# oneboard2.net
KiCad netlist of a schematic drawn in EAGLE
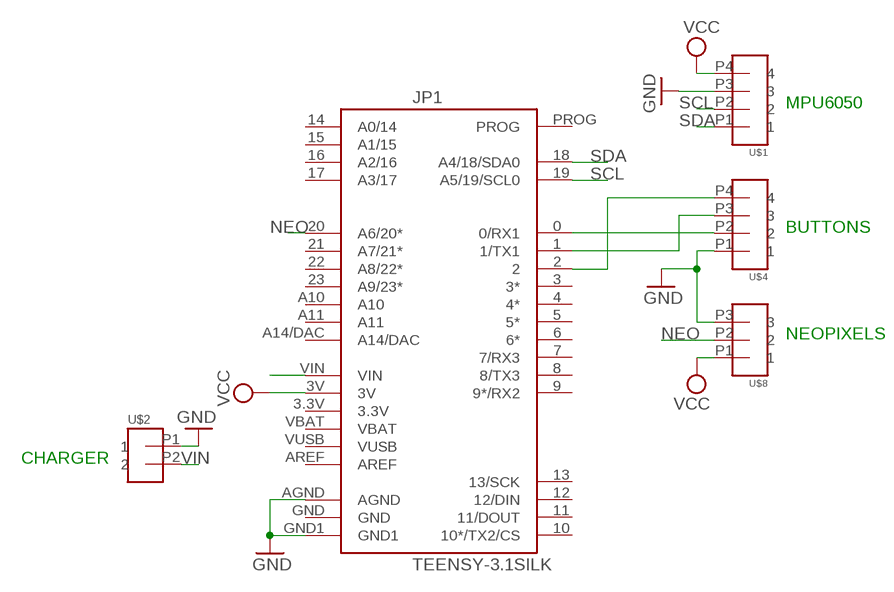
[diagram p0: schematic, sheet 1]

(export (version "E")
  (design (tool "Eeschema 10.0.6"))
  (components
    (comp (ref "JP1")
      (value "TEENSY-3.1SILK")
      (footprint "eagle-import:TEENSY-3.1")
      (libsource (lib "eagle-import") (part "TEENSY-3.1SILK"))
    )
    (comp (ref "U$1")
      (value "PTSM0,4-HH-2,5-SMD-R44")
      (footprint "eagle-import:M04_SMD_RIGHT")
      (libsource (lib "eagle-import") (part "PTSM0,4-HH-2,5-SMD-R44"))
    )
    (comp (ref "U$2")
      (value "PTSM0,2-HH-2,5-SMD-R32")
      (footprint "eagle-import:M02_SMD_RIGHT")
      (libsource (lib "eagle-import") (part "PTSM0,2-HH-2,5-SMD-R32"))
    )
    (comp (ref "U$4")
      (value "PTSM0,4-HH-2,5-SMD-R44")
      (footprint "eagle-import:M04_SMD_RIGHT")
      (libsource (lib "eagle-import") (part "PTSM0,4-HH-2,5-SMD-R44"))
    )
    (comp (ref "U$8")
      (value "PTSM0,3-HH-2,5-SMD-R44")
      (footprint "eagle-import:M03_SMD_RIGHT")
      (libsource (lib "eagle-import") (part "PTSM0,3-HH-2,5-SMD-R44"))
    )
  )
  (nets
    (net (code "1") (name "/NEO") (class "Default")
      (node (ref "JP1") (pin "20") (pinfunction "A6/20*_20") (pintype "bidirectional"))
      (node (ref "U$8") (pin "P2") (pinfunction "2_P2") (pintype "bidirectional"))
    )
    (net (code "2") (name "/SCL") (class "Default")
      (node (ref "JP1") (pin "19") (pinfunction "A5/19/SCL0_19") (pintype "bidirectional"))
      (node (ref "U$1") (pin "P2") (pinfunction "2_P2") (pintype "bidirectional"))
    )
    (net (code "3") (name "/SDA") (class "Default")
      (node (ref "JP1") (pin "18") (pinfunction "A4/18/SDA0_18") (pintype "bidirectional"))
      (node (ref "U$1") (pin "P1") (pinfunction "1_P1") (pintype "bidirectional"))
    )
    (net (code "4") (name "/VIN") (class "Default")
      (node (ref "JP1") (pin "VIN") (pinfunction "VIN_VIN") (pintype "bidirectional"))
      (node (ref "U$2") (pin "P2") (pinfunction "2_P2") (pintype "bidirectional"))
    )
    (net (code "5") (name "GND") (class "Default")
      (node (ref "JP1") (pin "AGND") (pinfunction "AGND_AGND") (pintype "bidirectional"))
      (node (ref "JP1") (pin "GND1") (pinfunction "GND1_GND1") (pintype "bidirectional"))
      (node (ref "U$1") (pin "P3") (pinfunction "3_P3") (pintype "bidirectional"))
      (node (ref "U$2") (pin "P1") (pinfunction "1_P1") (pintype "bidirectional"))
      (node (ref "U$4") (pin "P1") (pinfunction "1_P1") (pintype "bidirectional"))
      (node (ref "U$8") (pin "P3") (pinfunction "3_P3") (pintype "bidirectional"))
    )
    (net (code "6") (name "Net-(JP1-0{slash}RX1)") (class "Default")
      (node (ref "JP1") (pin "0") (pinfunction "0/RX1_0") (pintype "bidirectional"))
      (node (ref "U$4") (pin "P2") (pinfunction "2_P2") (pintype "bidirectional"))
    )
    (net (code "7") (name "Net-(JP1-1{slash}TX1)") (class "Default")
      (node (ref "JP1") (pin "1") (pinfunction "1/TX1_1") (pintype "bidirectional"))
      (node (ref "U$4") (pin "P3") (pinfunction "3_P3") (pintype "bidirectional"))
    )
    (net (code "8") (name "Net-(U$4-4)") (class "Default")
      (node (ref "JP1") (pin "2") (pinfunction "2_2") (pintype "bidirectional"))
      (node (ref "U$4") (pin "P4") (pinfunction "4_P4") (pintype "bidirectional"))
    )
    (net (code "9") (name "VCC") (class "Default")
      (node (ref "JP1") (pin "3V") (pinfunction "3V_3V") (pintype "bidirectional"))
      (node (ref "U$1") (pin "P4") (pinfunction "4_P4") (pintype "bidirectional"))
      (node (ref "U$8") (pin "P1") (pinfunction "1_P1") (pintype "bidirectional"))
    )
    (net (code "10") (name "unconnected-(JP1-3*-Pad3)") (class "Default")
      (node (ref "JP1") (pin "3") (pinfunction "3*_3") (pintype "bidirectional"))
    )
    (net (code "11") (name "unconnected-(JP1-4*-Pad4)") (class "Default")
      (node (ref "JP1") (pin "4") (pinfunction "4*_4") (pintype "bidirectional"))
    )
    (net (code "12") (name "unconnected-(JP1-5*-Pad5)") (class "Default")
      (node (ref "JP1") (pin "5") (pinfunction "5*_5") (pintype "bidirectional"))
    )
    (net (code "13") (name "unconnected-(JP1-6*-Pad6)") (class "Default")
      (node (ref "JP1") (pin "6") (pinfunction "6*_6") (pintype "bidirectional"))
    )
    (net (code "14") (name "unconnected-(JP1-7{slash}RX3-Pad7)") (class "Default")
      (node (ref "JP1") (pin "7") (pinfunction "7/RX3_7") (pintype "bidirectional"))
    )
    (net (code "15") (name "unconnected-(JP1-8{slash}TX3-Pad8)") (class "Default")
      (node (ref "JP1") (pin "8") (pinfunction "8/TX3_8") (pintype "bidirectional"))
    )
    (net (code "16") (name "unconnected-(JP1-9*{slash}RX2-Pad9)") (class "Default")
      (node (ref "JP1") (pin "9") (pinfunction "9*/RX2_9") (pintype "bidirectional"))
    )
    (net (code "17") (name "unconnected-(JP1-10*{slash}TX2{slash}CS-Pad10)") (class "Default")
      (node (ref "JP1") (pin "10") (pinfunction "10*/TX2/CS_10") (pintype "bidirectional"))
    )
    (net (code "18") (name "unconnected-(JP1-11{slash}DOUT-Pad11)") (class "Default")
      (node (ref "JP1") (pin "11") (pinfunction "11/DOUT_11") (pintype "bidirectional"))
    )
    (net (code "19") (name "unconnected-(JP1-12{slash}DIN-Pad12)") (class "Default")
      (node (ref "JP1") (pin "12") (pinfunction "12/DIN_12") (pintype "bidirectional"))
    )
    (net (code "20") (name "unconnected-(JP1-13{slash}SCK-Pad13)") (class "Default")
      (node (ref "JP1") (pin "13") (pinfunction "13/SCK_13") (pintype "bidirectional"))
    )
    (net (code "21") (name "unconnected-(JP1-A0{slash}14-Pad14)") (class "Default")
      (node (ref "JP1") (pin "14") (pinfunction "A0/14_14") (pintype "bidirectional"))
    )
    (net (code "22") (name "unconnected-(JP1-A1{slash}15-Pad15)") (class "Default")
      (node (ref "JP1") (pin "15") (pinfunction "A1/15_15") (pintype "bidirectional"))
    )
    (net (code "23") (name "unconnected-(JP1-A2{slash}16-Pad16)") (class "Default")
      (node (ref "JP1") (pin "16") (pinfunction "A2/16_16") (pintype "bidirectional"))
    )
    (net (code "24") (name "unconnected-(JP1-A3{slash}17-Pad17)") (class "Default")
      (node (ref "JP1") (pin "17") (pinfunction "A3/17_17") (pintype "bidirectional"))
    )
    (net (code "25") (name "unconnected-(JP1-A7{slash}21*-Pad21)") (class "Default")
      (node (ref "JP1") (pin "21") (pinfunction "A7/21*_21") (pintype "bidirectional"))
    )
    (net (code "26") (name "unconnected-(JP1-A8{slash}22*-Pad22)") (class "Default")
      (node (ref "JP1") (pin "22") (pinfunction "A8/22*_22") (pintype "bidirectional"))
    )
    (net (code "27") (name "unconnected-(JP1-A9{slash}23*-Pad23)") (class "Default")
      (node (ref "JP1") (pin "23") (pinfunction "A9/23*_23") (pintype "bidirectional"))
    )
    (net (code "28") (name "unconnected-(JP1-Pad3.3V)") (class "Default")
      (node (ref "JP1") (pin "3.3V") (pinfunction "3.3V_3.3V") (pintype "bidirectional"))
    )
    (net (code "29") (name "unconnected-(JP1-PadA10)") (class "Default")
      (node (ref "JP1") (pin "A10") (pinfunction "A10_A10") (pintype "bidirectional"))
    )
    (net (code "30") (name "unconnected-(JP1-PadA11)") (class "Default")
      (node (ref "JP1") (pin "A11") (pinfunction "A11_A11") (pintype "bidirectional"))
    )
    (net (code "31") (name "unconnected-(JP1-PadA14{slash}DAC)") (class "Default")
      (node (ref "JP1") (pin "A14/DAC") (pinfunction "A14/DAC_A14/DAC") (pintype "bidirectional"))
    )
    (net (code "32") (name "unconnected-(JP1-PadAREF)") (class "Default")
      (node (ref "JP1") (pin "AREF") (pinfunction "AREF_AREF") (pintype "bidirectional"))
    )
    (net (code "33") (name "unconnected-(JP1-PadGND)") (class "Default")
      (node (ref "JP1") (pin "GND") (pinfunction "GND_GND") (pintype "bidirectional"))
    )
    (net (code "34") (name "unconnected-(JP1-PadPROG)") (class "Default")
      (node (ref "JP1") (pin "PROG") (pinfunction "PROG_PROG") (pintype "bidirectional"))
    )
    (net (code "35") (name "unconnected-(JP1-PadVBAT)") (class "Default")
      (node (ref "JP1") (pin "VBAT") (pinfunction "VBAT_VBAT") (pintype "bidirectional"))
    )
    (net (code "36") (name "unconnected-(JP1-PadVUSB)") (class "Default")
      (node (ref "JP1") (pin "VUSB") (pinfunction "VUSB_VUSB") (pintype "bidirectional"))
    )
  )
)
